# dynamic_mic_preamp.net
KiCad netlist of a schematic drawn in EAGLE
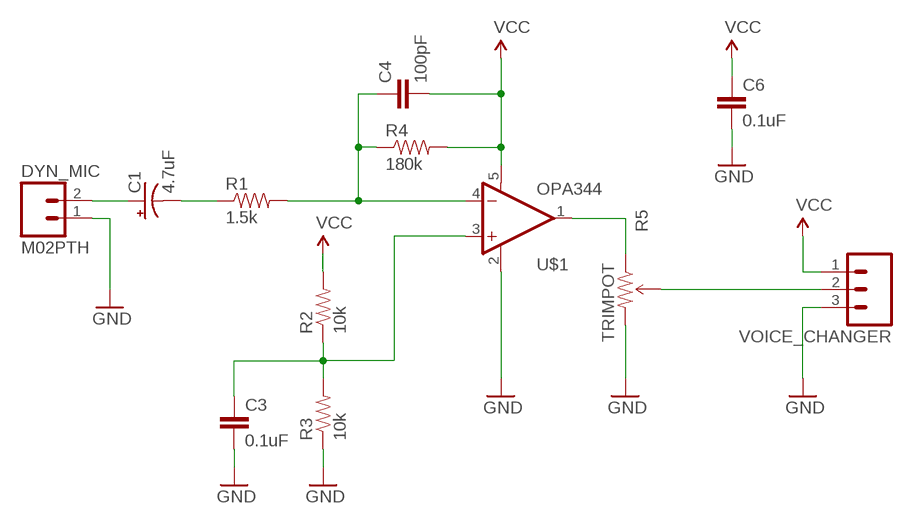
[diagram p0: schematic, sheet 1]

(export (version "E")
  (design (tool "Eeschema 10.0.6"))
  (components
    (comp (ref "C1")
      (value "4.7uF")
      (footprint "eagle-import:CPOL-RADIAL-100UF-25V")
      (libsource (lib "eagle-import") (part "CAP_POLPTH1"))
    )
    (comp (ref "C3")
      (value "0.1uF")
      (footprint "eagle-import:CAP-PTH-SMALL")
      (libsource (lib "eagle-import") (part "CAPPTH"))
    )
    (comp (ref "C4")
      (value "100pF")
      (footprint "eagle-import:CAP-PTH-SMALL")
      (libsource (lib "eagle-import") (part "CAPPTH"))
    )
    (comp (ref "C6")
      (value "0.1uF")
      (footprint "eagle-import:CAP-PTH-SMALL")
      (libsource (lib "eagle-import") (part "CAPPTH"))
    )
    (comp (ref "DYN_MIC")
      (value "M02PTH")
      (footprint "eagle-import:1X02")
      (libsource (lib "eagle-import") (part "M02PTH"))
    )
    (comp (ref "R1")
      (value "1.5k")
      (footprint "eagle-import:AXIAL-0.4")
      (libsource (lib "eagle-import") (part "RESISTORPTH-1/4W"))
    )
    (comp (ref "R2")
      (value "10k")
      (footprint "eagle-import:AXIAL-0.4")
      (libsource (lib "eagle-import") (part "RESISTORPTH-1/4W"))
    )
    (comp (ref "R3")
      (value "10k")
      (footprint "eagle-import:AXIAL-0.4")
      (libsource (lib "eagle-import") (part "RESISTORPTH-1/4W"))
    )
    (comp (ref "R4")
      (value "180k")
      (footprint "eagle-import:AXIAL-0.4")
      (libsource (lib "eagle-import") (part "RESISTORPTH-1/4W"))
    )
    (comp (ref "R5")
      (value "TRIMPOT")
      (footprint "eagle-import:TRIMPOT-5MM-V2")
      (libsource (lib "eagle-import") (part "TRIMPOT"))
    )
    (comp (ref "U$1")
      (value "OPA344")
      (footprint "eagle-import:SOT23-5")
      (libsource (lib "eagle-import") (part "OPA344"))
    )
    (comp (ref "VOICE_CHANGER")
      (value "M03PTH")
      (footprint "eagle-import:1X03")
      (libsource (lib "eagle-import") (part "M03PTH"))
    )
  )
  (nets
    (net (code "1") (name "GND") (class "Default")
      (node (ref "C3") (pin "2") (pinfunction "2_2") (pintype "passive"))
      (node (ref "C6") (pin "2") (pinfunction "2_2") (pintype "passive"))
      (node (ref "DYN_MIC") (pin "1") (pinfunction "1_1") (pintype "passive"))
      (node (ref "R3") (pin "P$1") (pinfunction "1_P$1") (pintype "passive"))
      (node (ref "R5") (pin "C") (pinfunction "CW_C") (pintype "passive"))
      (node (ref "U$1") (pin "2") (pinfunction "V-_2") (pintype "power_in"))
      (node (ref "VOICE_CHANGER") (pin "3") (pinfunction "3_3") (pintype "passive"))
    )
    (net (code "2") (name "Net-(C1-+)") (class "Default")
      (node (ref "C1") (pin "1") (pinfunction "+_1") (pintype "passive"))
      (node (ref "DYN_MIC") (pin "2") (pinfunction "2_2") (pintype "passive"))
    )
    (net (code "3") (name "Net-(C1--)") (class "Default")
      (node (ref "C1") (pin "2") (pinfunction "-_2") (pintype "passive"))
      (node (ref "R1") (pin "P$1") (pinfunction "1_P$1") (pintype "passive"))
    )
    (net (code "4") (name "Net-(R1-2)") (class "Default")
      (node (ref "C4") (pin "1") (pinfunction "1_1") (pintype "passive"))
      (node (ref "R1") (pin "P$2") (pinfunction "2_P$2") (pintype "passive"))
      (node (ref "R4") (pin "P$1") (pinfunction "1_P$1") (pintype "passive"))
      (node (ref "U$1") (pin "4") (pinfunction "-IN_4") (pintype "input"))
    )
    (net (code "5") (name "Net-(R2-1)") (class "Default")
      (node (ref "C3") (pin "1") (pinfunction "1_1") (pintype "passive"))
      (node (ref "R2") (pin "P$1") (pinfunction "1_P$1") (pintype "passive"))
      (node (ref "R3") (pin "P$2") (pinfunction "2_P$2") (pintype "passive"))
      (node (ref "U$1") (pin "3") (pinfunction "+IN_3") (pintype "input"))
    )
    (net (code "6") (name "Net-(R5-CCW)") (class "Default")
      (node (ref "R5") (pin "A") (pinfunction "CCW_A") (pintype "passive"))
      (node (ref "U$1") (pin "1") (pinfunction "OUT_1") (pintype "output"))
    )
    (net (code "7") (name "Net-(R5-WIPER)") (class "Default")
      (node (ref "R5") (pin "B") (pinfunction "WIPER_B") (pintype "passive"))
      (node (ref "VOICE_CHANGER") (pin "2") (pinfunction "2_2") (pintype "passive"))
    )
    (net (code "8") (name "VCC") (class "Default")
      (node (ref "C4") (pin "2") (pinfunction "2_2") (pintype "passive"))
      (node (ref "C6") (pin "1") (pinfunction "1_1") (pintype "passive"))
      (node (ref "R2") (pin "P$2") (pinfunction "2_P$2") (pintype "passive"))
      (node (ref "R4") (pin "P$2") (pinfunction "2_P$2") (pintype "passive"))
      (node (ref "U$1") (pin "5") (pinfunction "V+_5") (pintype "power_in"))
      (node (ref "VOICE_CHANGER") (pin "1") (pinfunction "1_1") (pintype "passive"))
    )
  )
)
